# LPDDR4.net
KiCad netlist of a schematic drawn in Altium Designer
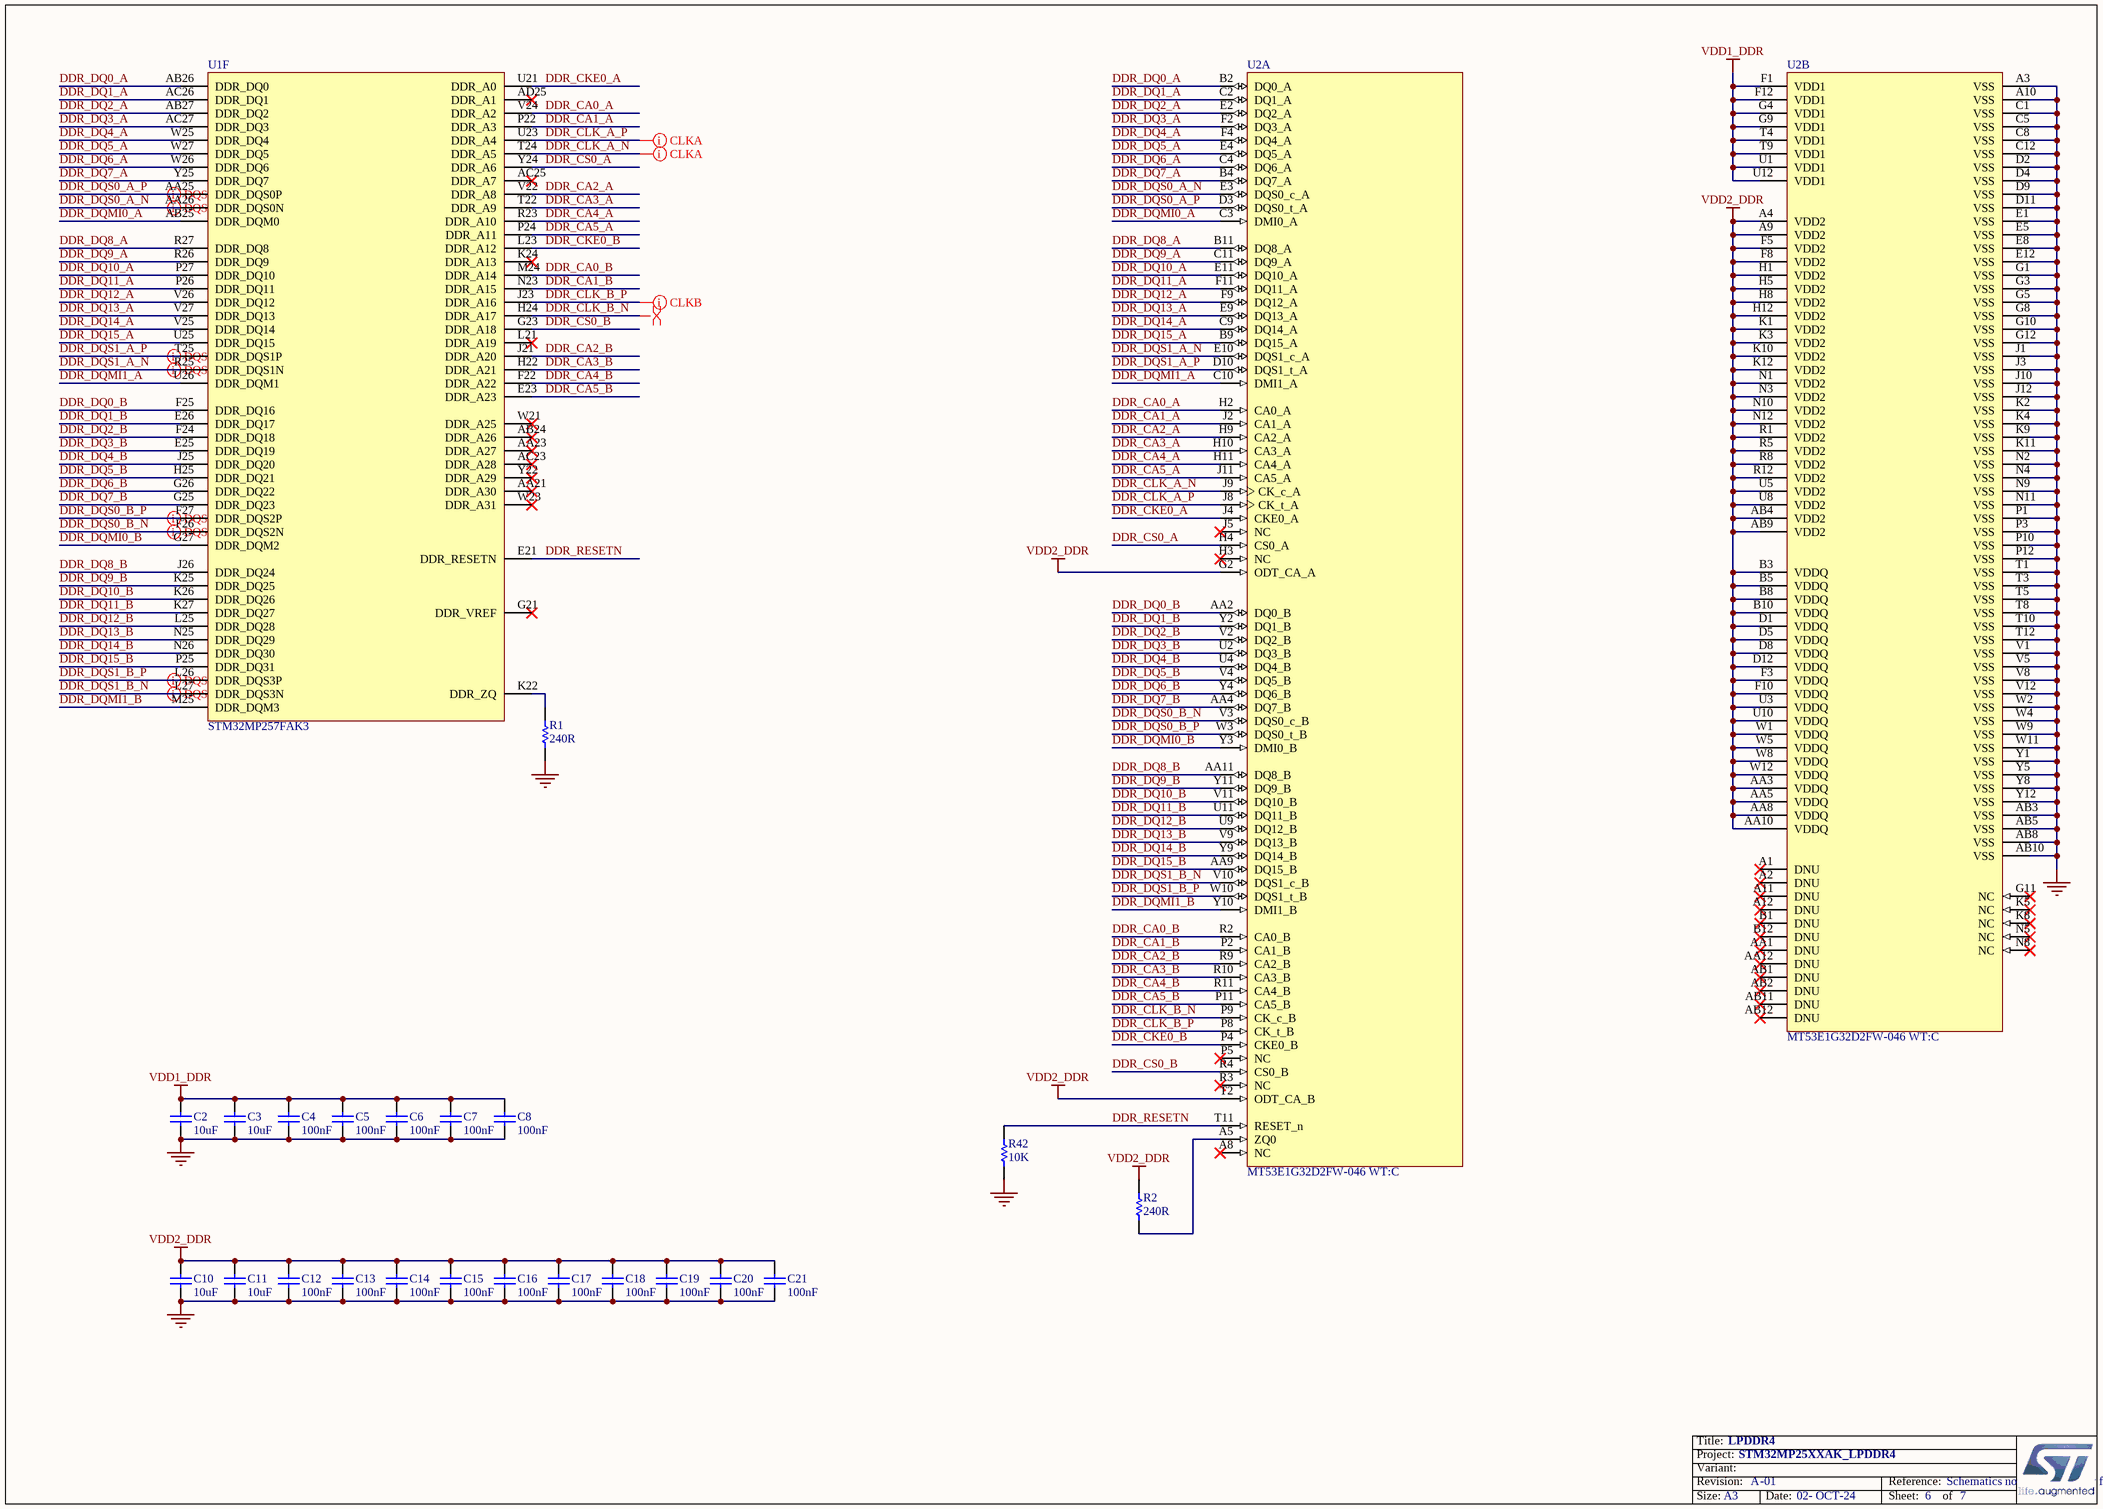
[diagram p0: LPDDR4.SchDoc]

(export (version "E")
  (design (tool "Eeschema 10.0.6"))
  (components
    (comp (ref "C2")
      (value "10uF")
      (footprint "C0603")
      (description "Capacitor, MLCC, 10uF, 6V3, X5R, 20%, 0603, T=0,8mm")
      (fields
        (field (name "INTERNAL_PART_NUMBER") "MCD-01341")
        (field (name "MANUFACTURER_PART_NUMBER") "GRM188R60J106ME47D")
        (field (name "PROVIDED_BY") "SUBCO")
      )
      (libsource (lib "MCD_PARTS_database") (part "Capacitor"))
    )
    (comp (ref "C3")
      (value "10uF")
      (footprint "C0603")
      (description "Capacitor, MLCC, 10uF, 6V3, X5R, 20%, 0603, T=0,8mm")
      (fields
        (field (name "INTERNAL_PART_NUMBER") "MCD-01341")
        (field (name "MANUFACTURER_PART_NUMBER") "GRM188R60J106ME47D")
        (field (name "PROVIDED_BY") "SUBCO")
      )
      (libsource (lib "MCD_PARTS_database") (part "Capacitor"))
    )
    (comp (ref "C4")
      (value "100nF")
      (footprint "C0402")
      (description "Capacitor, MLCC, 100nF, 16V, X7R, +/-10%, 0402, T=0.5mm")
      (fields (field (name "INTERNAL_PART_NUMBER") "MCD-00006") (field (name "MANUFACTURER") "YAGEO"))
      (libsource (lib "MCD_PARTS_database") (part "Capacitor"))
    )
    (comp (ref "C5")
      (value "100nF")
      (footprint "C0402")
      (description "Capacitor, MLCC, 100nF, 16V, X7R, +/-10%, 0402, T=0.5mm")
      (fields (field (name "INTERNAL_PART_NUMBER") "MCD-00006") (field (name "MANUFACTURER") "YAGEO"))
      (libsource (lib "MCD_PARTS_database") (part "Capacitor"))
    )
    (comp (ref "C6")
      (value "100nF")
      (footprint "C0402")
      (description "Capacitor, MLCC, 100nF, 16V, X7R, +/-10%, 0402, T=0.5mm")
      (fields (field (name "INTERNAL_PART_NUMBER") "MCD-00006") (field (name "MANUFACTURER") "YAGEO"))
      (libsource (lib "MCD_PARTS_database") (part "Capacitor"))
    )
    (comp (ref "C7")
      (value "100nF")
      (footprint "C0402")
      (description "Capacitor, MLCC, 100nF, 16V, X7R, +/-10%, 0402, T=0.5mm")
      (fields (field (name "INTERNAL_PART_NUMBER") "MCD-00006") (field (name "MANUFACTURER") "YAGEO"))
      (libsource (lib "MCD_PARTS_database") (part "Capacitor"))
    )
    (comp (ref "C8")
      (value "100nF")
      (footprint "C0402")
      (description "Capacitor, MLCC, 100nF, 16V, X7R, +/-10%, 0402, T=0.5mm")
      (fields (field (name "INTERNAL_PART_NUMBER") "MCD-00006") (field (name "MANUFACTURER") "YAGEO"))
      (libsource (lib "MCD_PARTS_database") (part "Capacitor"))
    )
    (comp (ref "C10")
      (value "10uF")
      (footprint "C0603")
      (description "Capacitor, MLCC, 10uF, 6V3, X5R, 20%, 0603, T=0,8mm")
      (fields
        (field (name "INTERNAL_PART_NUMBER") "MCD-01341")
        (field (name "MANUFACTURER_PART_NUMBER") "GRM188R60J106ME47D")
        (field (name "PROVIDED_BY") "SUBCO")
      )
      (libsource (lib "MCD_PARTS_database") (part "Capacitor"))
    )
    (comp (ref "C11")
      (value "10uF")
      (footprint "C0603")
      (description "Capacitor, MLCC, 10uF, 6V3, X5R, 20%, 0603, T=0,8mm")
      (fields
        (field (name "INTERNAL_PART_NUMBER") "MCD-01341")
        (field (name "MANUFACTURER_PART_NUMBER") "GRM188R60J106ME47D")
        (field (name "PROVIDED_BY") "SUBCO")
      )
      (libsource (lib "MCD_PARTS_database") (part "Capacitor"))
    )
    (comp (ref "C12")
      (value "100nF")
      (footprint "C0402")
      (description "Capacitor, MLCC, 100nF, 16V, X7R, +/-10%, 0402, T=0.5mm")
      (fields (field (name "INTERNAL_PART_NUMBER") "MCD-00006") (field (name "MANUFACTURER") "YAGEO"))
      (libsource (lib "MCD_PARTS_database") (part "Capacitor"))
    )
    (comp (ref "C13")
      (value "100nF")
      (footprint "C0402")
      (description "Capacitor, MLCC, 100nF, 16V, X7R, +/-10%, 0402, T=0.5mm")
      (fields (field (name "INTERNAL_PART_NUMBER") "MCD-00006") (field (name "MANUFACTURER") "YAGEO"))
      (libsource (lib "MCD_PARTS_database") (part "Capacitor"))
    )
    (comp (ref "C14")
      (value "100nF")
      (footprint "C0402")
      (description "Capacitor, MLCC, 100nF, 16V, X7R, +/-10%, 0402, T=0.5mm")
      (fields (field (name "INTERNAL_PART_NUMBER") "MCD-00006") (field (name "MANUFACTURER") "YAGEO"))
      (libsource (lib "MCD_PARTS_database") (part "Capacitor"))
    )
    (comp (ref "C15")
      (value "100nF")
      (footprint "C0402")
      (description "Capacitor, MLCC, 100nF, 16V, X7R, +/-10%, 0402, T=0.5mm")
      (fields (field (name "INTERNAL_PART_NUMBER") "MCD-00006") (field (name "MANUFACTURER") "YAGEO"))
      (libsource (lib "MCD_PARTS_database") (part "Capacitor"))
    )
    (comp (ref "C16")
      (value "100nF")
      (footprint "C0402")
      (description "Capacitor, MLCC, 100nF, 16V, X7R, +/-10%, 0402, T=0.5mm")
      (fields (field (name "INTERNAL_PART_NUMBER") "MCD-00006") (field (name "MANUFACTURER") "YAGEO"))
      (libsource (lib "MCD_PARTS_database") (part "Capacitor"))
    )
    (comp (ref "C17")
      (value "100nF")
      (footprint "C0402")
      (description "Capacitor, MLCC, 100nF, 16V, X7R, +/-10%, 0402, T=0.5mm")
      (fields (field (name "INTERNAL_PART_NUMBER") "MCD-00006") (field (name "MANUFACTURER") "YAGEO"))
      (libsource (lib "MCD_PARTS_database") (part "Capacitor"))
    )
    (comp (ref "C18")
      (value "100nF")
      (footprint "C0402")
      (description "Capacitor, MLCC, 100nF, 16V, X7R, +/-10%, 0402, T=0.5mm")
      (fields (field (name "INTERNAL_PART_NUMBER") "MCD-00006") (field (name "MANUFACTURER") "YAGEO"))
      (libsource (lib "MCD_PARTS_database") (part "Capacitor"))
    )
    (comp (ref "C19")
      (value "100nF")
      (footprint "C0402")
      (description "Capacitor, MLCC, 100nF, 16V, X7R, +/-10%, 0402, T=0.5mm")
      (fields (field (name "INTERNAL_PART_NUMBER") "MCD-00006") (field (name "MANUFACTURER") "YAGEO"))
      (libsource (lib "MCD_PARTS_database") (part "Capacitor"))
    )
    (comp (ref "C20")
      (value "100nF")
      (footprint "C0402")
      (description "Capacitor, MLCC, 100nF, 16V, X7R, +/-10%, 0402, T=0.5mm")
      (fields (field (name "INTERNAL_PART_NUMBER") "MCD-00006") (field (name "MANUFACTURER") "YAGEO"))
      (libsource (lib "MCD_PARTS_database") (part "Capacitor"))
    )
    (comp (ref "C21")
      (value "100nF")
      (footprint "C0402")
      (description "Capacitor, MLCC, 100nF, 16V, X7R, +/-10%, 0402, T=0.5mm")
      (fields (field (name "INTERNAL_PART_NUMBER") "MCD-00006") (field (name "MANUFACTURER") "YAGEO"))
      (libsource (lib "MCD_PARTS_database") (part "Capacitor"))
    )
    (comp (ref "R1")
      (value "240R")
      (footprint "R0201_H0P23")
      (description "Resistor, 240R, 0201, +/-1%, 1/20W")
      (fields (field (name "INTERNAL_PART_NUMBER") "MCD-02253") (field (name "MANUFACTURER") "YAGEO"))
      (libsource (lib "MCD_PARTS_database") (part "Resistor"))
    )
    (comp (ref "R2")
      (value "240R")
      (footprint "R0201_H0P23")
      (description "Resistor, 240R, 0201, +/-1%, 1/20W")
      (fields (field (name "INTERNAL_PART_NUMBER") "MCD-02253") (field (name "MANUFACTURER") "YAGEO"))
      (libsource (lib "MCD_PARTS_database") (part "Resistor"))
    )
    (comp (ref "R42")
      (value "10K")
      (footprint "R0402")
      (description "Resistor, 10K, 0402, +/-1%, 1/16W")
      (fields (field (name "INTERNAL_PART_NUMBER") "MCD-00053") (field (name "BMS_PART_NUMBER") "9131590"))
      (libsource (lib "MCD_PARTS_database") (part "Resistor"))
    )
    (comp (ref "U1")
      (value "STM32MP257FAK3")
      (footprint "ICC_TFBGA424_14X14_P050_H1P20_CODE-B0A2")
      (description "MPU , 2xCortex-A35@1.5GHz, Cortex-M33@400MHz, TFBGA 14x14, pitch 0.5, 808 KB SRAM, With Crypto")
      (fields
        (field (name "INTERNAL_PART_NUMBER") "MCD-03375")
        (field (name "MANUFACTURER") "STMICROELECTRONICS")
      )
      (libsource (lib "MCD_PARTS_database") (part "STM32MP257FAK3"))
    )
    (comp (ref "U2")
      (value "MT53E1G32D2FW-046 WT:C")
      (footprint "ICC_TFBGA200_10X14P5_P080_H1P05_PS0P3")
      (description "Memory, LPDDR4 SDRAM,1V8, 32Gbit, 2133MHz")
      (fields (field (name "INTERNAL_PART_NUMBER") "MCD-04160") (field (name "MANUFACTURER") "MICRON"))
      (libsource (lib "MCD_PARTS_database") (part "MT53E1G32D2FW-046 WT{colon}C"))
    )
  )
  (nets
    (net (code "1") (name "/DDR_CA0_A") (class "Default")
      (node (ref "U1") (pin "V24") (pinfunction "DDR_A2_V24") (pintype "passive"))
      (node (ref "U2") (pin "H2") (pinfunction "CA0_A_H2") (pintype "input"))
    )
    (net (code "2") (name "/DDR_CA0_B") (class "Default")
      (node (ref "U1") (pin "M24") (pinfunction "DDR_A14_M24") (pintype "passive"))
      (node (ref "U2") (pin "R2") (pinfunction "CA0_B_R2") (pintype "input"))
    )
    (net (code "3") (name "/DDR_CA1_A") (class "Default")
      (node (ref "U1") (pin "P22") (pinfunction "DDR_A3_P22") (pintype "passive"))
      (node (ref "U2") (pin "J2") (pinfunction "CA1_A_J2") (pintype "input"))
    )
    (net (code "4") (name "/DDR_CA1_B") (class "Default")
      (node (ref "U1") (pin "N23") (pinfunction "DDR_A15_N23") (pintype "passive"))
      (node (ref "U2") (pin "P2") (pinfunction "CA1_B_P2") (pintype "input"))
    )
    (net (code "5") (name "/DDR_CA2_A") (class "Default")
      (node (ref "U1") (pin "V22") (pinfunction "DDR_A8_V22") (pintype "passive"))
      (node (ref "U2") (pin "H9") (pinfunction "CA2_A_H9") (pintype "input"))
    )
    (net (code "6") (name "/DDR_CA2_B") (class "Default")
      (node (ref "U1") (pin "J21") (pinfunction "DDR_A20_J21") (pintype "passive"))
      (node (ref "U2") (pin "R9") (pinfunction "CA2_B_R9") (pintype "input"))
    )
    (net (code "7") (name "/DDR_CA3_A") (class "Default")
      (node (ref "U1") (pin "T22") (pinfunction "DDR_A9_T22") (pintype "passive"))
      (node (ref "U2") (pin "H10") (pinfunction "CA3_A_H10") (pintype "input"))
    )
    (net (code "8") (name "/DDR_CA3_B") (class "Default")
      (node (ref "U1") (pin "H22") (pinfunction "DDR_A21_H22") (pintype "passive"))
      (node (ref "U2") (pin "R10") (pinfunction "CA3_B_R10") (pintype "input"))
    )
    (net (code "9") (name "/DDR_CA4_A") (class "Default")
      (node (ref "U1") (pin "R23") (pinfunction "DDR_A10_R23") (pintype "passive"))
      (node (ref "U2") (pin "H11") (pinfunction "CA4_A_H11") (pintype "input"))
    )
    (net (code "10") (name "/DDR_CA4_B") (class "Default")
      (node (ref "U1") (pin "F22") (pinfunction "DDR_A22_F22") (pintype "passive"))
      (node (ref "U2") (pin "R11") (pinfunction "CA4_B_R11") (pintype "input"))
    )
    (net (code "11") (name "/DDR_CA5_A") (class "Default")
      (node (ref "U1") (pin "P24") (pinfunction "DDR_A11_P24") (pintype "passive"))
      (node (ref "U2") (pin "J11") (pinfunction "CA5_A_J11") (pintype "input"))
    )
    (net (code "12") (name "/DDR_CA5_B") (class "Default")
      (node (ref "U1") (pin "E23") (pinfunction "DDR_A23_E23") (pintype "passive"))
      (node (ref "U2") (pin "P11") (pinfunction "CA5_B_P11") (pintype "input"))
    )
    (net (code "13") (name "/DDR_CKE0_A") (class "Default")
      (node (ref "U1") (pin "U21") (pinfunction "DDR_A0_U21") (pintype "passive"))
      (node (ref "U2") (pin "J4") (pinfunction "CKE0_A_J4") (pintype "input"))
    )
    (net (code "14") (name "/DDR_CKE0_B") (class "Default")
      (node (ref "U1") (pin "L23") (pinfunction "DDR_A12_L23") (pintype "passive"))
      (node (ref "U2") (pin "P4") (pinfunction "CKE0_B_P4") (pintype "input"))
    )
    (net (code "15") (name "/DDR_CLK_A_N") (class "Default")
      (node (ref "U1") (pin "T24") (pinfunction "DDR_A5_T24") (pintype "passive"))
      (node (ref "U2") (pin "J9") (pinfunction "CK_c_A_J9") (pintype "input"))
    )
    (net (code "16") (name "/DDR_CLK_A_P") (class "Default")
      (node (ref "U1") (pin "U23") (pinfunction "DDR_A4_U23") (pintype "passive"))
      (node (ref "U2") (pin "J8") (pinfunction "CK_t_A_J8") (pintype "input"))
    )
    (net (code "17") (name "/DDR_CLK_B_N") (class "Default")
      (node (ref "U1") (pin "H24") (pinfunction "DDR_A17_H24") (pintype "passive"))
      (node (ref "U2") (pin "P9") (pinfunction "CK_c_B_P9") (pintype "input"))
    )
    (net (code "18") (name "/DDR_CLK_B_P") (class "Default")
      (node (ref "U1") (pin "J23") (pinfunction "DDR_A16_J23") (pintype "passive"))
      (node (ref "U2") (pin "P8") (pinfunction "CK_t_B_P8") (pintype "input"))
    )
    (net (code "19") (name "/DDR_CS0_A") (class "Default")
      (node (ref "U1") (pin "Y24") (pinfunction "DDR_A6_Y24") (pintype "passive"))
      (node (ref "U2") (pin "H4") (pinfunction "CS0_A_H4") (pintype "input"))
    )
    (net (code "20") (name "/DDR_CS0_B") (class "Default")
      (node (ref "U1") (pin "G23") (pinfunction "DDR_A18_G23") (pintype "passive"))
      (node (ref "U2") (pin "R4") (pinfunction "CS0_B_R4") (pintype "input"))
    )
    (net (code "21") (name "/DDR_DQ0_A") (class "Default")
      (node (ref "U1") (pin "AB26") (pinfunction "DDR_DQ0_AB26") (pintype "passive"))
      (node (ref "U2") (pin "B2") (pinfunction "DQ0_A_B2") (pintype "bidirectional"))
    )
    (net (code "22") (name "/DDR_DQ0_B") (class "Default")
      (node (ref "U1") (pin "F25") (pinfunction "DDR_DQ16_F25") (pintype "passive"))
      (node (ref "U2") (pin "AA2") (pinfunction "DQ0_B_AA2") (pintype "bidirectional"))
    )
    (net (code "23") (name "/DDR_DQ1_A") (class "Default")
      (node (ref "U1") (pin "AC26") (pinfunction "DDR_DQ1_AC26") (pintype "passive"))
      (node (ref "U2") (pin "C2") (pinfunction "DQ1_A_C2") (pintype "bidirectional"))
    )
    (net (code "24") (name "/DDR_DQ1_B") (class "Default")
      (node (ref "U1") (pin "E26") (pinfunction "DDR_DQ17_E26") (pintype "passive"))
      (node (ref "U2") (pin "Y2") (pinfunction "DQ1_B_Y2") (pintype "bidirectional"))
    )
    (net (code "25") (name "/DDR_DQ2_A") (class "Default")
      (node (ref "U1") (pin "AB27") (pinfunction "DDR_DQ2_AB27") (pintype "passive"))
      (node (ref "U2") (pin "E2") (pinfunction "DQ2_A_E2") (pintype "bidirectional"))
    )
    (net (code "26") (name "/DDR_DQ2_B") (class "Default")
      (node (ref "U1") (pin "F24") (pinfunction "DDR_DQ18_F24") (pintype "passive"))
      (node (ref "U2") (pin "V2") (pinfunction "DQ2_B_V2") (pintype "bidirectional"))
    )
    (net (code "27") (name "/DDR_DQ3_A") (class "Default")
      (node (ref "U1") (pin "AC27") (pinfunction "DDR_DQ3_AC27") (pintype "passive"))
      (node (ref "U2") (pin "F2") (pinfunction "DQ3_A_F2") (pintype "bidirectional"))
    )
    (net (code "28") (name "/DDR_DQ3_B") (class "Default")
      (node (ref "U1") (pin "E25") (pinfunction "DDR_DQ19_E25") (pintype "passive"))
      (node (ref "U2") (pin "U2") (pinfunction "DQ3_B_U2") (pintype "bidirectional"))
    )
    (net (code "29") (name "/DDR_DQ4_A") (class "Default")
      (node (ref "U1") (pin "W25") (pinfunction "DDR_DQ4_W25") (pintype "passive"))
      (node (ref "U2") (pin "F4") (pinfunction "DQ4_A_F4") (pintype "bidirectional"))
    )
    (net (code "30") (name "/DDR_DQ4_B") (class "Default")
      (node (ref "U1") (pin "J25") (pinfunction "DDR_DQ20_J25") (pintype "passive"))
      (node (ref "U2") (pin "U4") (pinfunction "DQ4_B_U4") (pintype "bidirectional"))
    )
    (net (code "31") (name "/DDR_DQ5_A") (class "Default")
      (node (ref "U1") (pin "W27") (pinfunction "DDR_DQ5_W27") (pintype "passive"))
      (node (ref "U2") (pin "E4") (pinfunction "DQ5_A_E4") (pintype "bidirectional"))
    )
    (net (code "32") (name "/DDR_DQ5_B") (class "Default")
      (node (ref "U1") (pin "H25") (pinfunction "DDR_DQ21_H25") (pintype "passive"))
      (node (ref "U2") (pin "V4") (pinfunction "DQ5_B_V4") (pintype "bidirectional"))
    )
    (net (code "33") (name "/DDR_DQ6_A") (class "Default")
      (node (ref "U1") (pin "W26") (pinfunction "DDR_DQ6_W26") (pintype "passive"))
      (node (ref "U2") (pin "C4") (pinfunction "DQ6_A_C4") (pintype "bidirectional"))
    )
    (net (code "34") (name "/DDR_DQ6_B") (class "Default")
      (node (ref "U1") (pin "G26") (pinfunction "DDR_DQ22_G26") (pintype "passive"))
      (node (ref "U2") (pin "Y4") (pinfunction "DQ6_B_Y4") (pintype "bidirectional"))
    )
    (net (code "35") (name "/DDR_DQ7_A") (class "Default")
      (node (ref "U1") (pin "Y25") (pinfunction "DDR_DQ7_Y25") (pintype "passive"))
      (node (ref "U2") (pin "B4") (pinfunction "DQ7_A_B4") (pintype "bidirectional"))
    )
    (net (code "36") (name "/DDR_DQ7_B") (class "Default")
      (node (ref "U1") (pin "G25") (pinfunction "DDR_DQ23_G25") (pintype "passive"))
      (node (ref "U2") (pin "AA4") (pinfunction "DQ7_B_AA4") (pintype "bidirectional"))
    )
    (net (code "37") (name "/DDR_DQ8_A") (class "Default")
      (node (ref "U1") (pin "R27") (pinfunction "DDR_DQ8_R27") (pintype "passive"))
      (node (ref "U2") (pin "B11") (pinfunction "DQ8_A_B11") (pintype "bidirectional"))
    )
    (net (code "38") (name "/DDR_DQ8_B") (class "Default")
      (node (ref "U1") (pin "J26") (pinfunction "DDR_DQ24_J26") (pintype "passive"))
      (node (ref "U2") (pin "AA11") (pinfunction "DQ8_B_AA11") (pintype "bidirectional"))
    )
    (net (code "39") (name "/DDR_DQ9_A") (class "Default")
      (node (ref "U1") (pin "R26") (pinfunction "DDR_DQ9_R26") (pintype "passive"))
      (node (ref "U2") (pin "C11") (pinfunction "DQ9_A_C11") (pintype "bidirectional"))
    )
    (net (code "40") (name "/DDR_DQ9_B") (class "Default")
      (node (ref "U1") (pin "K25") (pinfunction "DDR_DQ25_K25") (pintype "passive"))
      (node (ref "U2") (pin "Y11") (pinfunction "DQ9_B_Y11") (pintype "bidirectional"))
    )
    (net (code "41") (name "/DDR_DQ10_A") (class "Default")
      (node (ref "U1") (pin "P27") (pinfunction "DDR_DQ10_P27") (pintype "passive"))
      (node (ref "U2") (pin "E11") (pinfunction "DQ10_A_E11") (pintype "bidirectional"))
    )
    (net (code "42") (name "/DDR_DQ10_B") (class "Default")
      (node (ref "U1") (pin "K26") (pinfunction "DDR_DQ26_K26") (pintype "passive"))
      (node (ref "U2") (pin "V11") (pinfunction "DQ10_B_V11") (pintype "bidirectional"))
    )
    (net (code "43") (name "/DDR_DQ11_A") (class "Default")
      (node (ref "U1") (pin "P26") (pinfunction "DDR_DQ11_P26") (pintype "passive"))
      (node (ref "U2") (pin "F11") (pinfunction "DQ11_A_F11") (pintype "bidirectional"))
    )
    (net (code "44") (name "/DDR_DQ11_B") (class "Default")
      (node (ref "U1") (pin "K27") (pinfunction "DDR_DQ27_K27") (pintype "passive"))
      (node (ref "U2") (pin "U11") (pinfunction "DQ11_B_U11") (pintype "bidirectional"))
    )
    (net (code "45") (name "/DDR_DQ12_A") (class "Default")
      (node (ref "U1") (pin "V26") (pinfunction "DDR_DQ12_V26") (pintype "passive"))
      (node (ref "U2") (pin "F9") (pinfunction "DQ12_A_F9") (pintype "bidirectional"))
    )
    (net (code "46") (name "/DDR_DQ12_B") (class "Default")
      (node (ref "U1") (pin "L25") (pinfunction "DDR_DQ28_L25") (pintype "passive"))
      (node (ref "U2") (pin "U9") (pinfunction "DQ12_B_U9") (pintype "bidirectional"))
    )
    (net (code "47") (name "/DDR_DQ13_A") (class "Default")
      (node (ref "U1") (pin "V27") (pinfunction "DDR_DQ13_V27") (pintype "passive"))
      (node (ref "U2") (pin "E9") (pinfunction "DQ13_A_E9") (pintype "bidirectional"))
    )
    (net (code "48") (name "/DDR_DQ13_B") (class "Default")
      (node (ref "U1") (pin "N25") (pinfunction "DDR_DQ29_N25") (pintype "passive"))
      (node (ref "U2") (pin "V9") (pinfunction "DQ13_B_V9") (pintype "bidirectional"))
    )
    (net (code "49") (name "/DDR_DQ14_A") (class "Default")
      (node (ref "U1") (pin "V25") (pinfunction "DDR_DQ14_V25") (pintype "passive"))
      (node (ref "U2") (pin "C9") (pinfunction "DQ14_A_C9") (pintype "bidirectional"))
    )
    (net (code "50") (name "/DDR_DQ14_B") (class "Default")
      (node (ref "U1") (pin "N26") (pinfunction "DDR_DQ30_N26") (pintype "passive"))
      (node (ref "U2") (pin "Y9") (pinfunction "DQ14_B_Y9") (pintype "bidirectional"))
    )
    (net (code "51") (name "/DDR_DQ15_A") (class "Default")
      (node (ref "U1") (pin "U25") (pinfunction "DDR_DQ15_U25") (pintype "passive"))
      (node (ref "U2") (pin "B9") (pinfunction "DQ15_A_B9") (pintype "bidirectional"))
    )
    (net (code "52") (name "/DDR_DQ15_B") (class "Default")
      (node (ref "U1") (pin "P25") (pinfunction "DDR_DQ31_P25") (pintype "passive"))
      (node (ref "U2") (pin "AA9") (pinfunction "DQ15_B_AA9") (pintype "bidirectional"))
    )
    (net (code "53") (name "/DDR_DQMI0_A") (class "Default")
      (node (ref "U1") (pin "AB25") (pinfunction "DDR_DQM0_AB25") (pintype "passive"))
      (node (ref "U2") (pin "C3") (pinfunction "DMI0_A_C3") (pintype "input"))
    )
    (net (code "54") (name "/DDR_DQMI0_B") (class "Default")
      (node (ref "U1") (pin "G27") (pinfunction "DDR_DQM2_G27") (pintype "passive"))
      (node (ref "U2") (pin "Y3") (pinfunction "DMI0_B_Y3") (pintype "input"))
    )
    (net (code "55") (name "/DDR_DQMI1_A") (class "Default")
      (node (ref "U1") (pin "U26") (pinfunction "DDR_DQM1_U26") (pintype "passive"))
      (node (ref "U2") (pin "C10") (pinfunction "DMI1_A_C10") (pintype "input"))
    )
    (net (code "56") (name "/DDR_DQMI1_B") (class "Default")
      (node (ref "U1") (pin "M25") (pinfunction "DDR_DQM3_M25") (pintype "passive"))
      (node (ref "U2") (pin "Y10") (pinfunction "DMI1_B_Y10") (pintype "input"))
    )
    (net (code "57") (name "/DDR_DQS0_A_N") (class "Default")
      (node (ref "U1") (pin "AA26") (pinfunction "DDR_DQS0N_AA26") (pintype "passive"))
      (node (ref "U2") (pin "E3") (pinfunction "DQS0_c_A_E3") (pintype "bidirectional"))
    )
    (net (code "58") (name "/DDR_DQS0_A_P") (class "Default")
      (node (ref "U1") (pin "AA25") (pinfunction "DDR_DQS0P_AA25") (pintype "passive"))
      (node (ref "U2") (pin "D3") (pinfunction "DQS0_t_A_D3") (pintype "bidirectional"))
    )
    (net (code "59") (name "/DDR_DQS0_B_N") (class "Default")
      (node (ref "U1") (pin "F26") (pinfunction "DDR_DQS2N_F26") (pintype "passive"))
      (node (ref "U2") (pin "V3") (pinfunction "DQS0_c_B_V3") (pintype "bidirectional"))
    )
    (net (code "60") (name "/DDR_DQS0_B_P") (class "Default")
      (node (ref "U1") (pin "F27") (pinfunction "DDR_DQS2P_F27") (pintype "passive"))
      (node (ref "U2") (pin "W3") (pinfunction "DQS0_t_B_W3") (pintype "bidirectional"))
    )
    (net (code "61") (name "/DDR_DQS1_A_N") (class "Default")
      (node (ref "U1") (pin "R25") (pinfunction "DDR_DQS1N_R25") (pintype "passive"))
      (node (ref "U2") (pin "E10") (pinfunction "DQS1_c_A_E10") (pintype "bidirectional"))
    )
    (net (code "62") (name "/DDR_DQS1_A_P") (class "Default")
      (node (ref "U1") (pin "T25") (pinfunction "DDR_DQS1P_T25") (pintype "passive"))
      (node (ref "U2") (pin "D10") (pinfunction "DQS1_t_A_D10") (pintype "bidirectional"))
    )
    (net (code "63") (name "/DDR_DQS1_B_N") (class "Default")
      (node (ref "U1") (pin "L27") (pinfunction "DDR_DQS3N_L27") (pintype "passive"))
      (node (ref "U2") (pin "V10") (pinfunction "DQS1_c_B_V10") (pintype "bidirectional"))
    )
    (net (code "64") (name "/DDR_DQS1_B_P") (class "Default")
      (node (ref "U1") (pin "L26") (pinfunction "DDR_DQS3P_L26") (pintype "passive"))
      (node (ref "U2") (pin "W10") (pinfunction "DQS1_t_B_W10") (pintype "bidirectional"))
    )
    (net (code "65") (name "/DDR_RESETN") (class "Default")
      (node (ref "R42") (pin "2") (pinfunction "2_2") (pintype "passive"))
      (node (ref "U1") (pin "E21") (pinfunction "DDR_RESETN_E21") (pintype "passive"))
      (node (ref "U2") (pin "T11") (pinfunction "RESET_n_T11") (pintype "input"))
    )
    (net (code "66") (name "GND") (class "Default")
      (node (ref "C10") (pin "1") (pinfunction "1_1") (pintype "passive"))
      (node (ref "C11") (pin "1") (pinfunction "1_1") (pintype "passive"))
      (node (ref "C12") (pin "2") (pinfunction "2_2") (pintype "passive"))
      (node (ref "C13") (pin "2") (pinfunction "2_2") (pintype "passive"))
      (node (ref "C14") (pin "2") (pinfunction "2_2") (pintype "passive"))
      (node (ref "C15") (pin "2") (pinfunction "2_2") (pintype "passive"))
      (node (ref "C16") (pin "2") (pinfunction "2_2") (pintype "passive"))
      (node (ref "C17") (pin "2") (pinfunction "2_2") (pintype "passive"))
      (node (ref "C18") (pin "2") (pinfunction "2_2") (pintype "passive"))
      (node (ref "C19") (pin "2") (pinfunction "2_2") (pintype "passive"))
      (node (ref "C2") (pin "1") (pinfunction "1_1") (pintype "passive"))
      (node (ref "C20") (pin "2") (pinfunction "2_2") (pintype "passive"))
      (node (ref "C21") (pin "2") (pinfunction "2_2") (pintype "passive"))
      (node (ref "C3") (pin "1") (pinfunction "1_1") (pintype "passive"))
      (node (ref "C4") (pin "2") (pinfunction "2_2") (pintype "passive"))
      (node (ref "C5") (pin "2") (pinfunction "2_2") (pintype "passive"))
      (node (ref "C6") (pin "2") (pinfunction "2_2") (pintype "passive"))
      (node (ref "C7") (pin "2") (pinfunction "2_2") (pintype "passive"))
      (node (ref "C8") (pin "2") (pinfunction "2_2") (pintype "passive"))
      (node (ref "R1") (pin "1") (pinfunction "1_1") (pintype "passive"))
      (node (ref "R42") (pin "1") (pinfunction "1_1") (pintype "passive"))
      (node (ref "U2") (pin "A10") (pinfunction "VSS_A10") (pintype "power_in"))
      (node (ref "U2") (pin "A3") (pinfunction "VSS_A3") (pintype "power_in"))
      (node (ref "U2") (pin "AB10") (pinfunction "VSS_AB10") (pintype "passive"))
      (node (ref "U2") (pin "AB3") (pinfunction "VSS_AB3") (pintype "passive"))
      (node (ref "U2") (pin "AB5") (pinfunction "VSS_AB5") (pintype "passive"))
      (node (ref "U2") (pin "AB8") (pinfunction "VSS_AB8") (pintype "passive"))
      (node (ref "U2") (pin "C1") (pinfunction "VSS_C1") (pintype "power_in"))
      (node (ref "U2") (pin "C12") (pinfunction "VSS_C12") (pintype "power_in"))
      (node (ref "U2") (pin "C5") (pinfunction "VSS_C5") (pintype "power_in"))
      (node (ref "U2") (pin "C8") (pinfunction "VSS_C8") (pintype "power_in"))
      (node (ref "U2") (pin "D11") (pinfunction "VSS_D11") (pintype "power_in"))
      (node (ref "U2") (pin "D2") (pinfunction "VSS_D2") (pintype "power_in"))
      (node (ref "U2") (pin "D4") (pinfunction "VSS_D4") (pintype "power_in"))
      (node (ref "U2") (pin "D9") (pinfunction "VSS_D9") (pintype "power_in"))
      (node (ref "U2") (pin "E1") (pinfunction "VSS_E1") (pintype "power_in"))
      (node (ref "U2") (pin "E12") (pinfunction "VSS_E12") (pintype "power_in"))
      (node (ref "U2") (pin "E5") (pinfunction "VSS_E5") (pintype "power_in"))
      (node (ref "U2") (pin "E8") (pinfunction "VSS_E8") (pintype "power_in"))
      (node (ref "U2") (pin "G1") (pinfunction "VSS_G1") (pintype "power_in"))
      (node (ref "U2") (pin "G10") (pinfunction "VSS_G10") (pintype "power_in"))
      (node (ref "U2") (pin "G12") (pinfunction "VSS_G12") (pintype "power_in"))
      (node (ref "U2") (pin "G3") (pinfunction "VSS_G3") (pintype "power_in"))
      (node (ref "U2") (pin "G5") (pinfunction "VSS_G5") (pintype "power_in"))
      (node (ref "U2") (pin "G8") (pinfunction "VSS_G8") (pintype "power_in"))
      (node (ref "U2") (pin "J1") (pinfunction "VSS_J1") (pintype "power_in"))
      (node (ref "U2") (pin "J10") (pinfunction "VSS_J10") (pintype "power_in"))
      (node (ref "U2") (pin "J12") (pinfunction "VSS_J12") (pintype "power_in"))
      (node (ref "U2") (pin "J3") (pinfunction "VSS_J3") (pintype "power_in"))
      (node (ref "U2") (pin "K11") (pinfunction "VSS_K11") (pintype "passive"))
      (node (ref "U2") (pin "K2") (pinfunction "VSS_K2") (pintype "power_in"))
      (node (ref "U2") (pin "K4") (pinfunction "VSS_K4") (pintype "power_in"))
      (node (ref "U2") (pin "K9") (pinfunction "VSS_K9") (pintype "power_in"))
      (node (ref "U2") (pin "N11") (pinfunction "VSS_N11") (pintype "passive"))
      (node (ref "U2") (pin "N2") (pinfunction "VSS_N2") (pintype "passive"))
      (node (ref "U2") (pin "N4") (pinfunction "VSS_N4") (pintype "passive"))
      (node (ref "U2") (pin "N9") (pinfunction "VSS_N9") (pintype "passive"))
      (node (ref "U2") (pin "P1") (pinfunction "VSS_P1") (pintype "passive"))
      (node (ref "U2") (pin "P10") (pinfunction "VSS_P10") (pintype "power_in"))
      (node (ref "U2") (pin "P12") (pinfunction "VSS_P12") (pintype "passive"))
      (node (ref "U2") (pin "P3") (pinfunction "VSS_P3") (pintype "power_in"))
      (node (ref "U2") (pin "T1") (pinfunction "VSS_T1") (pintype "passive"))
      (node (ref "U2") (pin "T10") (pinfunction "VSS_T10") (pintype "passive"))
      (node (ref "U2") (pin "T12") (pinfunction "VSS_T12") (pintype "passive"))
      (node (ref "U2") (pin "T3") (pinfunction "VSS_T3") (pintype "passive"))
      (node (ref "U2") (pin "T5") (pinfunction "VSS_T5") (pintype "passive"))
      (node (ref "U2") (pin "T8") (pinfunction "VSS_T8") (pintype "passive"))
      (node (ref "U2") (pin "V1") (pinfunction "VSS_V1") (pintype "power_in"))
      (node (ref "U2") (pin "V12") (pinfunction "VSS_V12") (pintype "passive"))
      (node (ref "U2") (pin "V5") (pinfunction "VSS_V5") (pintype "power_in"))
      (node (ref "U2") (pin "V8") (pinfunction "VSS_V8") (pintype "passive"))
      (node (ref "U2") (pin "W11") (pinfunction "VSS_W11") (pintype "passive"))
      (node (ref "U2") (pin "W2") (pinfunction "VSS_W2") (pintype "passive"))
      (node (ref "U2") (pin "W4") (pinfunction "VSS_W4") (pintype "passive"))
      (node (ref "U2") (pin "W9") (pinfunction "VSS_W9") (pintype "passive"))
      (node (ref "U2") (pin "Y1") (pinfunction "VSS_Y1") (pintype "passive"))
      (node (ref "U2") (pin "Y12") (pinfunction "VSS_Y12") (pintype "passive"))
      (node (ref "U2") (pin "Y5") (pinfunction "VSS_Y5") (pintype "passive"))
      (node (ref "U2") (pin "Y8") (pinfunction "VSS_Y8") (pintype "passive"))
    )
    (net (code "67") (name "Net-(U1F-DDR_ZQ)") (class "Default")
      (node (ref "R1") (pin "2") (pinfunction "2_2") (pintype "passive"))
      (node (ref "U1") (pin "K22") (pinfunction "DDR_ZQ_K22") (pintype "passive"))
    )
    (net (code "68") (name "Net-(U2A-ZQ0)") (class "Default")
      (node (ref "R2") (pin "1") (pinfunction "1_1") (pintype "passive"))
      (node (ref "U2") (pin "A5") (pinfunction "ZQ0_A5") (pintype "input"))
    )
    (net (code "69") (name "VDD1_DDR") (class "Default")
      (node (ref "C2") (pin "2") (pinfunction "2_2") (pintype "passive"))
      (node (ref "C3") (pin "2") (pinfunction "2_2") (pintype "passive"))
      (node (ref "C4") (pin "1") (pinfunction "1_1") (pintype "passive"))
      (node (ref "C5") (pin "1") (pinfunction "1_1") (pintype "passive"))
      (node (ref "C6") (pin "1") (pinfunction "1_1") (pintype "passive"))
      (node (ref "C7") (pin "1") (pinfunction "1_1") (pintype "passive"))
      (node (ref "C8") (pin "1") (pinfunction "1_1") (pintype "passive"))
      (node (ref "U2") (pin "F1") (pinfunction "VDD1_F1") (pintype "power_in"))
      (node (ref "U2") (pin "F12") (pinfunction "VDD1_F12") (pintype "power_in"))
      (node (ref "U2") (pin "G4") (pinfunction "VDD1_G4") (pintype "power_in"))
      (node (ref "U2") (pin "G9") (pinfunction "VDD1_G9") (pintype "power_in"))
      (node (ref "U2") (pin "T4") (pinfunction "VDD1_T4") (pintype "power_in"))
      (node (ref "U2") (pin "T9") (pinfunction "VDD1_T9") (pintype "power_in"))
      (node (ref "U2") (pin "U1") (pinfunction "VDD1_U1") (pintype "power_in"))
      (node (ref "U2") (pin "U12") (pinfunction "VDD1_U12") (pintype "power_in"))
    )
    (net (code "70") (name "VDD2_DDR") (class "Default")
      (node (ref "C10") (pin "2") (pinfunction "2_2") (pintype "passive"))
      (node (ref "C11") (pin "2") (pinfunction "2_2") (pintype "passive"))
      (node (ref "C12") (pin "1") (pinfunction "1_1") (pintype "passive"))
      (node (ref "C13") (pin "1") (pinfunction "1_1") (pintype "passive"))
      (node (ref "C14") (pin "1") (pinfunction "1_1") (pintype "passive"))
      (node (ref "C15") (pin "1") (pinfunction "1_1") (pintype "passive"))
      (node (ref "C16") (pin "1") (pinfunction "1_1") (pintype "passive"))
      (node (ref "C17") (pin "1") (pinfunction "1_1") (pintype "passive"))
      (node (ref "C18") (pin "1") (pinfunction "1_1") (pintype "passive"))
      (node (ref "C19") (pin "1") (pinfunction "1_1") (pintype "passive"))
      (node (ref "C20") (pin "1") (pinfunction "1_1") (pintype "passive"))
      (node (ref "C21") (pin "1") (pinfunction "1_1") (pintype "passive"))
      (node (ref "R2") (pin "2") (pinfunction "2_2") (pintype "passive"))
      (node (ref "U2") (pin "A4") (pinfunction "VDD2_A4") (pintype "power_in"))
      (node (ref "U2") (pin "A9") (pinfunction "VDD2_A9") (pintype "power_in"))
      (node (ref "U2") (pin "AA10") (pinfunction "VDDQ_AA10") (pintype "power_in"))
      (node (ref "U2") (pin "AA3") (pinfunction "VDDQ_AA3") (pintype "power_in"))
      (node (ref "U2") (pin "AA5") (pinfunction "VDDQ_AA5") (pintype "power_in"))
      (node (ref "U2") (pin "AA8") (pinfunction "VDDQ_AA8") (pintype "power_in"))
      (node (ref "U2") (pin "AB4") (pinfunction "VDD2_AB4") (pintype "power_in"))
      (node (ref "U2") (pin "AB9") (pinfunction "VDD2_AB9") (pintype "power_in"))
      (node (ref "U2") (pin "B10") (pinfunction "VDDQ_B10") (pintype "power_in"))
      (node (ref "U2") (pin "B3") (pinfunction "VDDQ_B3") (pintype "power_in"))
      (node (ref "U2") (pin "B5") (pinfunction "VDDQ_B5") (pintype "power_in"))
      (node (ref "U2") (pin "B8") (pinfunction "VDDQ_B8") (pintype "power_in"))
      (node (ref "U2") (pin "D1") (pinfunction "VDDQ_D1") (pintype "power_in"))
      (node (ref "U2") (pin "D12") (pinfunction "VDDQ_D12") (pintype "power_in"))
      (node (ref "U2") (pin "D5") (pinfunction "VDDQ_D5") (pintype "power_in"))
      (node (ref "U2") (pin "D8") (pinfunction "VDDQ_D8") (pintype "power_in"))
      (node (ref "U2") (pin "F10") (pinfunction "VDDQ_F10") (pintype "power_in"))
      (node (ref "U2") (pin "F3") (pinfunction "VDDQ_F3") (pintype "power_in"))
      (node (ref "U2") (pin "F5") (pinfunction "VDD2_F5") (pintype "power_in"))
      (node (ref "U2") (pin "F8") (pinfunction "VDD2_F8") (pintype "power_in"))
      (node (ref "U2") (pin "G2") (pinfunction "ODT_CA_A_G2") (pintype "input"))
      (node (ref "U2") (pin "H1") (pinfunction "VDD2_H1") (pintype "power_in"))
      (node (ref "U2") (pin "H12") (pinfunction "VDD2_H12") (pintype "power_in"))
      (node (ref "U2") (pin "H5") (pinfunction "VDD2_H5") (pintype "power_in"))
      (node (ref "U2") (pin "H8") (pinfunction "VDD2_H8") (pintype "power_in"))
      (node (ref "U2") (pin "K1") (pinfunction "VDD2_K1") (pintype "power_in"))
      (node (ref "U2") (pin "K10") (pinfunction "VDD2_K10") (pintype "power_in"))
      (node (ref "U2") (pin "K12") (pinfunction "VDD2_K12") (pintype "power_in"))
      (node (ref "U2") (pin "K3") (pinfunction "VDD2_K3") (pintype "power_in"))
      (node (ref "U2") (pin "N1") (pinfunction "VDD2_N1") (pintype "power_in"))
      (node (ref "U2") (pin "N10") (pinfunction "VDD2_N10") (pintype "power_in"))
      (node (ref "U2") (pin "N12") (pinfunction "VDD2_N12") (pintype "power_in"))
      (node (ref "U2") (pin "N3") (pinfunction "VDD2_N3") (pintype "power_in"))
      (node (ref "U2") (pin "R1") (pinfunction "VDD2_R1") (pintype "power_in"))
      (node (ref "U2") (pin "R12") (pinfunction "VDD2_R12") (pintype "power_in"))
      (node (ref "U2") (pin "R5") (pinfunction "VDD2_R5") (pintype "power_in"))
      (node (ref "U2") (pin "R8") (pinfunction "VDD2_R8") (pintype "power_in"))
      (node (ref "U2") (pin "T2") (pinfunction "ODT_CA_B_T2") (pintype "input"))
      (node (ref "U2") (pin "U10") (pinfunction "VDDQ_U10") (pintype "power_in"))
      (node (ref "U2") (pin "U3") (pinfunction "VDDQ_U3") (pintype "power_in"))
      (node (ref "U2") (pin "U5") (pinfunction "VDD2_U5") (pintype "power_in"))
      (node (ref "U2") (pin "U8") (pinfunction "VDD2_U8") (pintype "power_in"))
      (node (ref "U2") (pin "W1") (pinfunction "VDDQ_W1") (pintype "power_in"))
      (node (ref "U2") (pin "W12") (pinfunction "VDDQ_W12") (pintype "power_in"))
      (node (ref "U2") (pin "W5") (pinfunction "VDDQ_W5") (pintype "power_in"))
      (node (ref "U2") (pin "W8") (pinfunction "VDDQ_W8") (pintype "power_in"))
    )
    (net (code "71") (name "unconnected-(U1F-DDR_A1-PadAD25)") (class "Default")
      (node (ref "U1") (pin "AD25") (pinfunction "DDR_A1_AD25") (pintype "passive+no_connect"))
    )
    (net (code "72") (name "unconnected-(U1F-DDR_A7-PadAC25)") (class "Default")
      (node (ref "U1") (pin "AC25") (pinfunction "DDR_A7_AC25") (pintype "passive+no_connect"))
    )
    (net (code "73") (name "unconnected-(U1F-DDR_A13-PadK24)") (class "Default")
      (node (ref "U1") (pin "K24") (pinfunction "DDR_A13_K24") (pintype "passive+no_connect"))
    )
    (net (code "74") (name "unconnected-(U1F-DDR_A19-PadL21)") (class "Default")
      (node (ref "U1") (pin "L21") (pinfunction "DDR_A19_L21") (pintype "passive+no_connect"))
    )
    (net (code "75") (name "unconnected-(U1F-DDR_A25-PadW21)") (class "Default")
      (node (ref "U1") (pin "W21") (pinfunction "DDR_A25_W21") (pintype "passive+no_connect"))
    )
    (net (code "76") (name "unconnected-(U1F-DDR_A26-PadAB24)") (class "Default")
      (node (ref "U1") (pin "AB24") (pinfunction "DDR_A26_AB24") (pintype "passive+no_connect"))
    )
    (net (code "77") (name "unconnected-(U1F-DDR_A27-PadAA23)") (class "Default")
      (node (ref "U1") (pin "AA23") (pinfunction "DDR_A27_AA23") (pintype "passive+no_connect"))
    )
    (net (code "78") (name "unconnected-(U1F-DDR_A28-PadAC23)") (class "Default")
      (node (ref "U1") (pin "AC23") (pinfunction "DDR_A28_AC23") (pintype "passive+no_connect"))
    )
    (net (code "79") (name "unconnected-(U1F-DDR_A29-PadY22)") (class "Default")
      (node (ref "U1") (pin "Y22") (pinfunction "DDR_A29_Y22") (pintype "passive+no_connect"))
    )
    (net (code "80") (name "unconnected-(U1F-DDR_A30-PadAA21)") (class "Default")
      (node (ref "U1") (pin "AA21") (pinfunction "DDR_A30_AA21") (pintype "passive+no_connect"))
    )
    (net (code "81") (name "unconnected-(U1F-DDR_A31-PadW23)") (class "Default")
      (node (ref "U1") (pin "W23") (pinfunction "DDR_A31_W23") (pintype "passive+no_connect"))
    )
    (net (code "82") (name "unconnected-(U1F-DDR_VREF-PadG21)") (class "Default")
      (node (ref "U1") (pin "G21") (pinfunction "DDR_VREF_G21") (pintype "passive+no_connect"))
    )
    (net (code "83") (name "unconnected-(U2A-NC-PadA8)") (class "Default")
      (node (ref "U2") (pin "A8") (pinfunction "NC_A8") (pintype "input+no_connect"))
    )
    (net (code "84") (name "unconnected-(U2A-NC-PadH3)") (class "Default")
      (node (ref "U2") (pin "H3") (pinfunction "NC_H3") (pintype "input+no_connect"))
    )
    (net (code "85") (name "unconnected-(U2A-NC-PadJ5)") (class "Default")
      (node (ref "U2") (pin "J5") (pinfunction "NC_J5") (pintype "input+no_connect"))
    )
    (net (code "86") (name "unconnected-(U2A-NC-PadP5)") (class "Default")
      (node (ref "U2") (pin "P5") (pinfunction "NC_P5") (pintype "input+no_connect"))
    )
    (net (code "87") (name "unconnected-(U2A-NC-PadR3)") (class "Default")
      (node (ref "U2") (pin "R3") (pinfunction "NC_R3") (pintype "input+no_connect"))
    )
    (net (code "88") (name "unconnected-(U2B-DNU-PadA1)") (class "Default")
      (node (ref "U2") (pin "A1") (pinfunction "DNU_A1") (pintype "passive+no_connect"))
    )
    (net (code "89") (name "unconnected-(U2B-DNU-PadA2)") (class "Default")
      (node (ref "U2") (pin "A2") (pinfunction "DNU_A2") (pintype "passive+no_connect"))
    )
    (net (code "90") (name "unconnected-(U2B-DNU-PadA11)") (class "Default")
      (node (ref "U2") (pin "A11") (pinfunction "DNU_A11") (pintype "passive+no_connect"))
    )
    (net (code "91") (name "unconnected-(U2B-DNU-PadA12)") (class "Default")
      (node (ref "U2") (pin "A12") (pinfunction "DNU_A12") (pintype "passive+no_connect"))
    )
    (net (code "92") (name "unconnected-(U2B-DNU-PadAA1)") (class "Default")
      (node (ref "U2") (pin "AA1") (pinfunction "DNU_AA1") (pintype "passive+no_connect"))
    )
    (net (code "93") (name "unconnected-(U2B-DNU-PadAA12)") (class "Default")
      (node (ref "U2") (pin "AA12") (pinfunction "DNU_AA12") (pintype "passive+no_connect"))
    )
    (net (code "94") (name "unconnected-(U2B-DNU-PadAB1)") (class "Default")
      (node (ref "U2") (pin "AB1") (pinfunction "DNU_AB1") (pintype "passive+no_connect"))
    )
    (net (code "95") (name "unconnected-(U2B-DNU-PadAB2)") (class "Default")
      (node (ref "U2") (pin "AB2") (pinfunction "DNU_AB2") (pintype "passive+no_connect"))
    )
    (net (code "96") (name "unconnected-(U2B-DNU-PadAB11)") (class "Default")
      (node (ref "U2") (pin "AB11") (pinfunction "DNU_AB11") (pintype "passive+no_connect"))
    )
    (net (code "97") (name "unconnected-(U2B-DNU-PadAB12)") (class "Default")
      (node (ref "U2") (pin "AB12") (pinfunction "DNU_AB12") (pintype "passive+no_connect"))
    )
    (net (code "98") (name "unconnected-(U2B-DNU-PadB1)") (class "Default")
      (node (ref "U2") (pin "B1") (pinfunction "DNU_B1") (pintype "passive+no_connect"))
    )
    (net (code "99") (name "unconnected-(U2B-DNU-PadB12)") (class "Default")
      (node (ref "U2") (pin "B12") (pinfunction "DNU_B12") (pintype "passive+no_connect"))
    )
    (net (code "100") (name "unconnected-(U2B-NC-PadG11)") (class "Default")
      (node (ref "U2") (pin "G11") (pinfunction "NC_G11") (pintype "input+no_connect"))
    )
    (net (code "101") (name "unconnected-(U2B-NC-PadK5)") (class "Default")
      (node (ref "U2") (pin "K5") (pinfunction "NC_K5") (pintype "input+no_connect"))
    )
    (net (code "102") (name "unconnected-(U2B-NC-PadK8)") (class "Default")
      (node (ref "U2") (pin "K8") (pinfunction "NC_K8") (pintype "input+no_connect"))
    )
    (net (code "103") (name "unconnected-(U2B-NC-PadN5)") (class "Default")
      (node (ref "U2") (pin "N5") (pinfunction "NC_N5") (pintype "input+no_connect"))
    )
    (net (code "104") (name "unconnected-(U2B-NC-PadN8)") (class "Default")
      (node (ref "U2") (pin "N8") (pinfunction "NC_N8") (pintype "input+no_connect"))
    )
  )
)
